# norbi_lm_pl_interface.net
KiCad netlist of a schematic drawn in Altium Designer
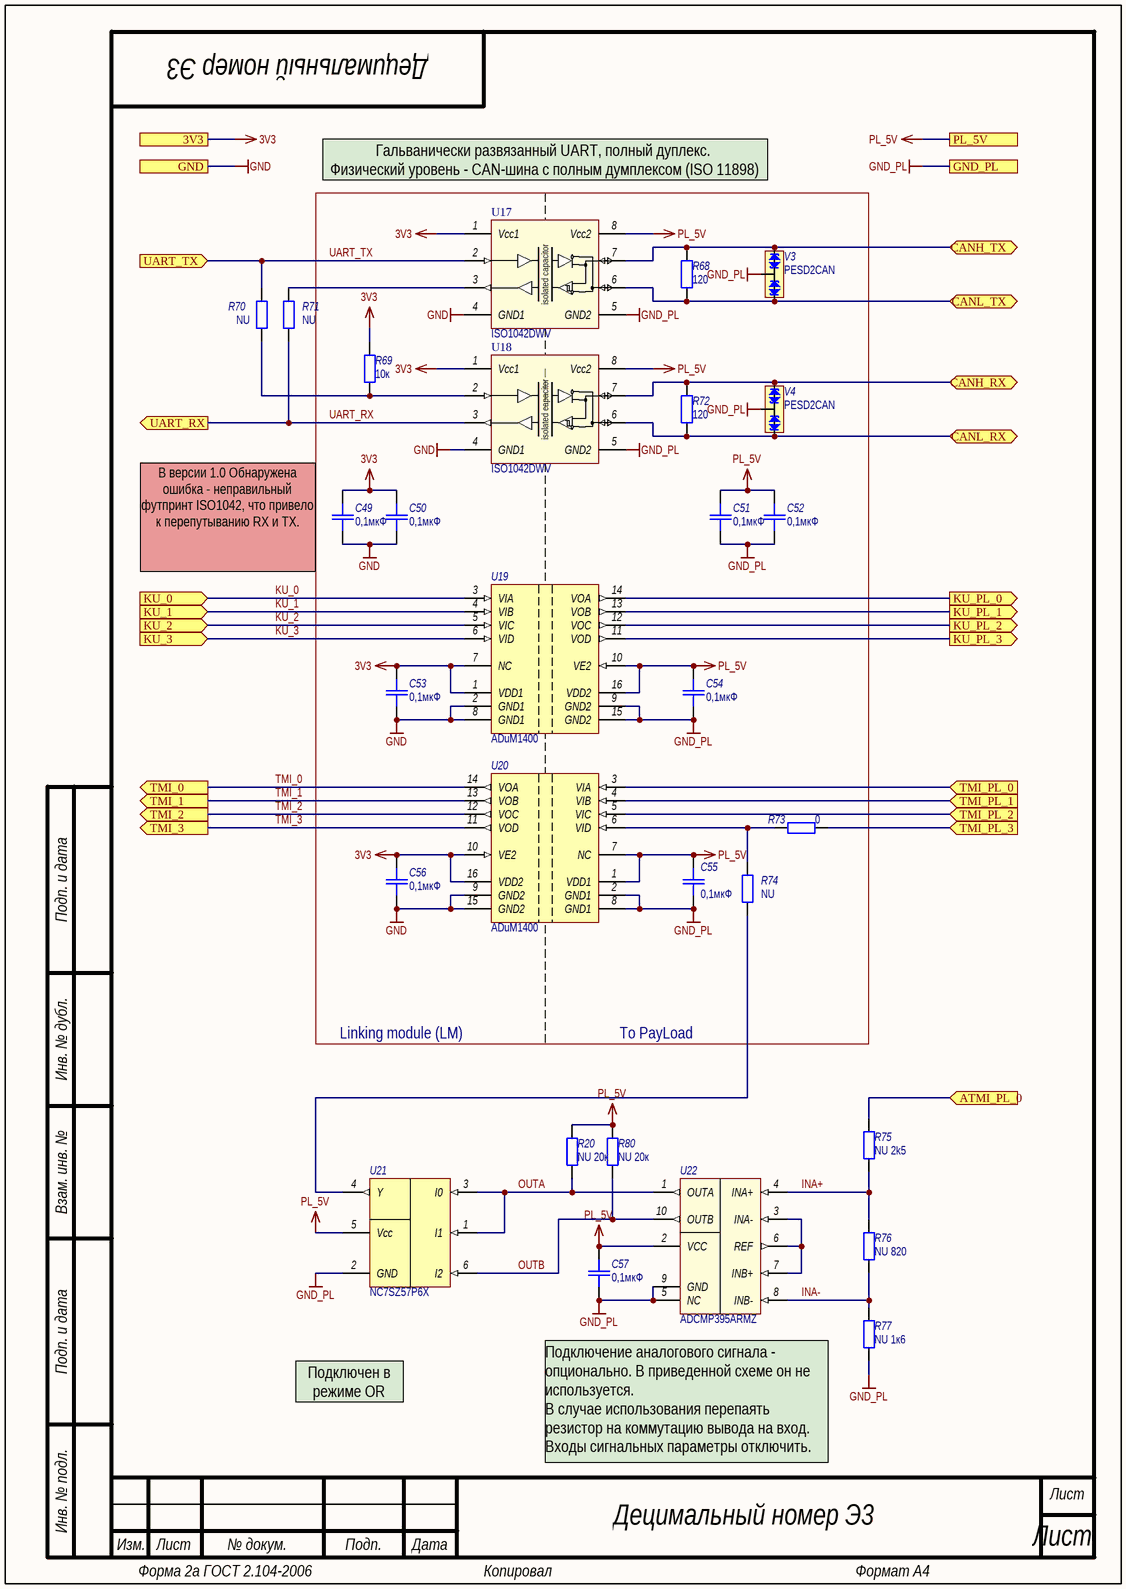
[diagram p0: norbi_lm_pl_interface.SchDoc]

(export (version "E")
  (design (tool "Eeschema 10.0.6"))
  (components
    (comp (ref "C49")
      (value "0,1мкФ")
      (footprint "CR-0603")
      (description "Конденсатор для поверхностного монтажа")
      (libsource (lib "my_passive") (part "C_smd"))
    )
    (comp (ref "C50")
      (value "0,1мкФ")
      (footprint "CR-0603")
      (description "Конденсатор для поверхностного монтажа")
      (libsource (lib "my_passive") (part "C_smd"))
    )
    (comp (ref "C51")
      (value "0,1мкФ")
      (footprint "CR-0603")
      (description "Конденсатор для поверхностного монтажа")
      (libsource (lib "my_passive") (part "C_smd"))
    )
    (comp (ref "C52")
      (value "0,1мкФ")
      (footprint "CR-0603")
      (description "Конденсатор для поверхностного монтажа")
      (libsource (lib "my_passive") (part "C_smd"))
    )
    (comp (ref "C53")
      (value "0,1мкФ")
      (footprint "CR-0603")
      (description "Конденсатор для поверхностного монтажа")
      (libsource (lib "my_passive") (part "C_smd"))
    )
    (comp (ref "C54")
      (value "0,1мкФ")
      (footprint "CR-0603")
      (description "Конденсатор для поверхностного монтажа")
      (libsource (lib "my_passive") (part "C_smd"))
    )
    (comp (ref "C55")
      (value "0,1мкФ")
      (footprint "CR-0603")
      (description "Конденсатор для поверхностного монтажа")
      (libsource (lib "my_passive") (part "C_smd"))
    )
    (comp (ref "C56")
      (value "0,1мкФ")
      (footprint "CR-0603")
      (description "Конденсатор для поверхностного монтажа")
      (libsource (lib "my_passive") (part "C_smd"))
    )
    (comp (ref "C57")
      (value "0,1мкФ")
      (footprint "CR-0603")
      (description "Конденсатор для поверхностного монтажа")
      (libsource (lib "my_passive") (part "C_smd"))
    )
    (comp (ref "R20")
      (value "NU 20к")
      (footprint "CR-0603")
      (description "Резистор для поверхностного монтажа")
      (libsource (lib "my_passive") (part "R_smd"))
    )
    (comp (ref "R68")
      (value "120")
      (footprint "CR-0603")
      (description "Резистор для поверхностного монтажа")
      (libsource (lib "my_passive") (part "R_smd"))
    )
    (comp (ref "R69")
      (value "10к")
      (footprint "CR-0603")
      (description "Резистор для поверхностного монтажа")
      (libsource (lib "") (part "R_smd_1"))
    )
    (comp (ref "R70")
      (value "NU")
      (footprint "CR-0603")
      (description "Резистор для поверхностного монтажа")
      (libsource (lib "my_passive") (part "R_smd"))
    )
    (comp (ref "R71")
      (value "NU")
      (footprint "CR-0603")
      (description "Резистор для поверхностного монтажа")
      (libsource (lib "my_passive") (part "R_smd"))
    )
    (comp (ref "R72")
      (value "120")
      (footprint "CR-0603")
      (description "Резистор для поверхностного монтажа")
      (libsource (lib "my_passive") (part "R_smd"))
    )
    (comp (ref "R73")
      (value "0")
      (footprint "CR-0603")
      (description "Резистор для поверхностного монтажа")
      (libsource (lib "") (part "R_smd_2"))
    )
    (comp (ref "R74")
      (value "NU")
      (footprint "CR-0603")
      (description "Резистор для поверхностного монтажа")
      (libsource (lib "my_passive") (part "R_smd"))
    )
    (comp (ref "R75")
      (value "NU 2k5")
      (footprint "CR-0603")
      (description "Резистор для поверхностного монтажа")
      (libsource (lib "my_passive") (part "R_smd"))
    )
    (comp (ref "R76")
      (value "NU 820")
      (footprint "CR-0603")
      (description "Резистор для поверхностного монтажа")
      (libsource (lib "my_passive") (part "R_smd"))
    )
    (comp (ref "R77")
      (value "NU 1к6")
      (footprint "CR-0603")
      (description "Резистор для поверхностного монтажа")
      (libsource (lib "my_passive") (part "R_smd"))
    )
    (comp (ref "R80")
      (value "NU 20к")
      (footprint "CR-0603")
      (description "Резистор для поверхностного монтажа")
      (libsource (lib "my_passive") (part "R_smd"))
    )
    (comp (ref "U17")
      (value "ISO1042")
      (footprint "SOIC-8-WIDE")
      (description "Isolated CAN Transceiver")
      (fields (field (name "НАИМЕНОВАНИЕ") "ISO1042DWV"))
      (libsource (lib "my_integrated_circuit") (part "ISO1042"))
    )
    (comp (ref "U18")
      (value "ISO1042")
      (footprint "SOIC-8-WIDE")
      (description "Isolated CAN Transceiver")
      (fields (field (name "НАИМЕНОВАНИЕ") "ISO1042DWV"))
      (libsource (lib "my_integrated_circuit") (part "ISO1042"))
    )
    (comp (ref "U19")
      (value "ADuM1400")
      (footprint "SOIC-16-WIDE")
      (description "Quad Channel Digital Isolator, 2.5 KV rms Insulation Rating")
      (fields (field (name "НАИМЕНОВАНИЕ") "ADuM1400"))
      (libsource (lib "") (part "ADuM1400_1"))
    )
    (comp (ref "U20")
      (value "ADuM1400")
      (footprint "SOIC-16-WIDE")
      (description "Quad Channel Digital Isolator, 2.5 KV rms Insulation Rating")
      (fields (field (name "НАИМЕНОВАНИЕ") "ADuM1400"))
      (libsource (lib "my_integrated_circuit") (part "ADuM1400"))
    )
    (comp (ref "U21")
      (value "NC7SZ57P6X")
      (footprint "SC70 6-Lead")
      (description "Universal Configurable 2-Input\r\nLogic Gates")
      (fields (field (name "НАИМЕНОВАНИЕ") "NC7SZ57P6X"))
      (libsource (lib "my_integrated_circuit") (part "NC7SZ57"))
    )
    (comp (ref "U22")
      (value "ADCMP395ARMZ")
      (footprint "MSOP-10")
      (description "Dual Comparators with Accurate Reference Output")
      (fields (field (name "НАИМЕНОВАНИЕ") "ADCMP395ARMZ"))
      (libsource (lib "my_integrated_circuit") (part "ADCMP395"))
    )
    (comp (ref "V3")
      (value "PESD2CAN")
      (footprint "SOT-23")
      (description "CAN bus ESD protection diode")
      (fields (field (name "НАИМЕНОВАНИЕ") "PESD2CAN"))
      (libsource (lib "my_semicond") (part "PESD2CAN"))
    )
    (comp (ref "V4")
      (value "PESD2CAN")
      (footprint "SOT-23")
      (description "CAN bus ESD protection diode")
      (fields (field (name "НАИМЕНОВАНИЕ") "PESD2CAN"))
      (libsource (lib "my_semicond") (part "PESD2CAN"))
    )
  )
  (nets
    (net (code "1") (name "/ATMI_PL_0") (class "Default")
      (node (ref "R75") (pin "2") (pinfunction "2_2") (pintype "passive"))
    )
    (net (code "2") (name "/CANH_RX") (class "Default")
      (node (ref "R72") (pin "2") (pinfunction "2_2") (pintype "passive"))
      (node (ref "U18") (pin "7") (pinfunction "CANH_7") (pintype "bidirectional"))
      (node (ref "V4") (pin "1") (pinfunction "C1_1") (pintype "passive"))
    )
    (net (code "3") (name "/CANH_TX") (class "Default")
      (node (ref "R68") (pin "2") (pinfunction "2_2") (pintype "passive"))
      (node (ref "U17") (pin "7") (pinfunction "CANH_7") (pintype "bidirectional"))
      (node (ref "V3") (pin "1") (pinfunction "C1_1") (pintype "passive"))
    )
    (net (code "4") (name "/CANL_RX") (class "Default")
      (node (ref "R72") (pin "1") (pinfunction "1_1") (pintype "passive"))
      (node (ref "U18") (pin "6") (pinfunction "CANL_6") (pintype "bidirectional"))
      (node (ref "V4") (pin "2") (pinfunction "C2_2") (pintype "passive"))
    )
    (net (code "5") (name "/CANL_TX") (class "Default")
      (node (ref "R68") (pin "1") (pinfunction "1_1") (pintype "passive"))
      (node (ref "U17") (pin "6") (pinfunction "CANL_6") (pintype "bidirectional"))
      (node (ref "V3") (pin "2") (pinfunction "C2_2") (pintype "passive"))
    )
    (net (code "6") (name "/INA+") (class "Default")
      (node (ref "R75") (pin "1") (pinfunction "1_1") (pintype "passive"))
      (node (ref "R76") (pin "2") (pinfunction "2_2") (pintype "passive"))
      (node (ref "U22") (pin "4") (pinfunction "INA+_4") (pintype "input"))
    )
    (net (code "7") (name "/INA-") (class "Default")
      (node (ref "R76") (pin "1") (pinfunction "1_1") (pintype "passive"))
      (node (ref "R77") (pin "2") (pinfunction "2_2") (pintype "passive"))
      (node (ref "U22") (pin "8") (pinfunction "INB-_8") (pintype "input"))
    )
    (net (code "8") (name "/KU_0") (class "Default")
      (node (ref "U19") (pin "3") (pinfunction "VIA_3") (pintype "input"))
    )
    (net (code "9") (name "/KU_1") (class "Default")
      (node (ref "U19") (pin "4") (pinfunction "VIB_4") (pintype "input"))
    )
    (net (code "10") (name "/KU_2") (class "Default")
      (node (ref "U19") (pin "5") (pinfunction "VIC_5") (pintype "input"))
    )
    (net (code "11") (name "/KU_3") (class "Default")
      (node (ref "U19") (pin "6") (pinfunction "VID_6") (pintype "input"))
    )
    (net (code "12") (name "/KU_PL_0") (class "Default")
      (node (ref "U19") (pin "14") (pinfunction "VOA_14") (pintype "output"))
    )
    (net (code "13") (name "/KU_PL_1") (class "Default")
      (node (ref "U19") (pin "13") (pinfunction "VOB_13") (pintype "output"))
    )
    (net (code "14") (name "/KU_PL_2") (class "Default")
      (node (ref "U19") (pin "12") (pinfunction "VOC_12") (pintype "output"))
    )
    (net (code "15") (name "/KU_PL_3") (class "Default")
      (node (ref "U19") (pin "11") (pinfunction "VOD_11") (pintype "output"))
    )
    (net (code "16") (name "/OUTA") (class "Default")
      (node (ref "R20") (pin "1") (pinfunction "1_1") (pintype "passive"))
      (node (ref "U21") (pin "1") (pinfunction "I1_1") (pintype "input"))
      (node (ref "U21") (pin "3") (pinfunction "I0_3") (pintype "input"))
      (node (ref "U22") (pin "1") (pinfunction "OUTA_1") (pintype "output"))
    )
    (net (code "17") (name "/OUTB") (class "Default")
      (node (ref "R80") (pin "1") (pinfunction "1_1") (pintype "passive"))
      (node (ref "U21") (pin "6") (pinfunction "I2_6") (pintype "input"))
      (node (ref "U22") (pin "10") (pinfunction "OUTB_10") (pintype "output"))
    )
    (net (code "18") (name "/TMI_0") (class "Default")
      (node (ref "U20") (pin "14") (pinfunction "VOA_14") (pintype "output"))
    )
    (net (code "19") (name "/TMI_1") (class "Default")
      (node (ref "U20") (pin "13") (pinfunction "VOB_13") (pintype "output"))
    )
    (net (code "20") (name "/TMI_2") (class "Default")
      (node (ref "U20") (pin "12") (pinfunction "VOC_12") (pintype "output"))
    )
    (net (code "21") (name "/TMI_3") (class "Default")
      (node (ref "U20") (pin "11") (pinfunction "VOD_11") (pintype "output"))
    )
    (net (code "22") (name "/TMI_PL_0") (class "Default")
      (node (ref "U20") (pin "3") (pinfunction "VIA_3") (pintype "input"))
    )
    (net (code "23") (name "/TMI_PL_1") (class "Default")
      (node (ref "U20") (pin "4") (pinfunction "VIB_4") (pintype "input"))
    )
    (net (code "24") (name "/TMI_PL_2") (class "Default")
      (node (ref "U20") (pin "5") (pinfunction "VIC_5") (pintype "input"))
    )
    (net (code "25") (name "/TMI_PL_3") (class "Default")
      (node (ref "R73") (pin "1") (pinfunction "1_1") (pintype "passive"))
    )
    (net (code "26") (name "/UART_RX") (class "Default")
      (node (ref "R71") (pin "1") (pinfunction "1_1") (pintype "passive"))
      (node (ref "U18") (pin "3") (pinfunction "RXD_3") (pintype "output"))
    )
    (net (code "27") (name "/UART_TX") (class "Default")
      (node (ref "R70") (pin "2") (pinfunction "2_2") (pintype "passive"))
      (node (ref "U17") (pin "2") (pinfunction "TXD_2") (pintype "input"))
    )
    (net (code "28") (name "3V3") (class "Default")
      (node (ref "C49") (pin "2") (pinfunction "2_2") (pintype "passive"))
      (node (ref "C50") (pin "2") (pinfunction "2_2") (pintype "passive"))
      (node (ref "C53") (pin "2") (pinfunction "2_2") (pintype "passive"))
      (node (ref "C56") (pin "2") (pinfunction "2_2") (pintype "passive"))
      (node (ref "R69") (pin "1") (pinfunction "1_1") (pintype "passive"))
      (node (ref "U17") (pin "1") (pinfunction "Vcc1_1") (pintype "power_in"))
      (node (ref "U18") (pin "1") (pinfunction "Vcc1_1") (pintype "power_in"))
      (node (ref "U19") (pin "1") (pinfunction "VDD1_1") (pintype "power_in"))
      (node (ref "U19") (pin "7") (pinfunction "NC_7") (pintype "passive"))
      (node (ref "U20") (pin "10") (pinfunction "VE2_10") (pintype "input"))
      (node (ref "U20") (pin "16") (pinfunction "VDD2_16") (pintype "power_in"))
    )
    (net (code "29") (name "GND") (class "Default")
      (node (ref "C49") (pin "1") (pinfunction "1_1") (pintype "passive"))
      (node (ref "C50") (pin "1") (pinfunction "1_1") (pintype "passive"))
      (node (ref "C53") (pin "1") (pinfunction "1_1") (pintype "passive"))
      (node (ref "C56") (pin "1") (pinfunction "1_1") (pintype "passive"))
      (node (ref "U17") (pin "4") (pinfunction "GND1_4") (pintype "power_in"))
      (node (ref "U18") (pin "4") (pinfunction "GND1_4") (pintype "power_in"))
      (node (ref "U19") (pin "2") (pinfunction "GND1_2") (pintype "power_in"))
      (node (ref "U19") (pin "8") (pinfunction "GND1_8") (pintype "power_in"))
      (node (ref "U20") (pin "15") (pinfunction "GND2_15") (pintype "power_in"))
      (node (ref "U20") (pin "9") (pinfunction "GND2_9") (pintype "power_in"))
    )
    (net (code "30") (name "GND_PL") (class "Default")
      (node (ref "C51") (pin "1") (pinfunction "1_1") (pintype "passive"))
      (node (ref "C52") (pin "1") (pinfunction "1_1") (pintype "passive"))
      (node (ref "C54") (pin "1") (pinfunction "1_1") (pintype "passive"))
      (node (ref "C55") (pin "1") (pinfunction "1_1") (pintype "passive"))
      (node (ref "C57") (pin "1") (pinfunction "1_1") (pintype "passive"))
      (node (ref "R77") (pin "1") (pinfunction "1_1") (pintype "passive"))
      (node (ref "U17") (pin "5") (pinfunction "GND2_5") (pintype "power_in"))
      (node (ref "U18") (pin "5") (pinfunction "GND2_5") (pintype "power_in"))
      (node (ref "U19") (pin "15") (pinfunction "GND2_15") (pintype "power_in"))
      (node (ref "U19") (pin "9") (pinfunction "GND2_9") (pintype "power_in"))
      (node (ref "U20") (pin "2") (pinfunction "GND1_2") (pintype "power_in"))
      (node (ref "U20") (pin "8") (pinfunction "GND1_8") (pintype "power_in"))
      (node (ref "U21") (pin "2") (pinfunction "GND_2") (pintype "power_in"))
      (node (ref "U22") (pin "5") (pinfunction "NC_5") (pintype "passive"))
      (node (ref "U22") (pin "9") (pinfunction "GND_9") (pintype "power_in"))
      (node (ref "V3") (pin "3") (pinfunction "CC_3") (pintype "passive"))
      (node (ref "V4") (pin "3") (pinfunction "CC_3") (pintype "passive"))
    )
    (net (code "31") (name "Net-(U17-RXD)") (class "Default")
      (node (ref "R71") (pin "2") (pinfunction "2_2") (pintype "passive"))
      (node (ref "U17") (pin "3") (pinfunction "RXD_3") (pintype "output"))
    )
    (net (code "32") (name "Net-(U18-TXD)") (class "Default")
      (node (ref "R69") (pin "2") (pinfunction "2_2") (pintype "passive"))
      (node (ref "R70") (pin "1") (pinfunction "1_1") (pintype "passive"))
      (node (ref "U18") (pin "2") (pinfunction "TXD_2") (pintype "input"))
    )
    (net (code "33") (name "Net-(U20-VID)") (class "Default")
      (node (ref "R73") (pin "2") (pinfunction "2_2") (pintype "passive"))
      (node (ref "R74") (pin "2") (pinfunction "2_2") (pintype "passive"))
      (node (ref "U20") (pin "6") (pinfunction "VID_6") (pintype "input"))
    )
    (net (code "34") (name "Net-(U21-Y)") (class "Default")
      (node (ref "R74") (pin "1") (pinfunction "1_1") (pintype "passive"))
      (node (ref "U21") (pin "4") (pinfunction "Y_4") (pintype "output"))
    )
    (net (code "35") (name "Net-(U22-INA-)") (class "Default")
      (node (ref "U22") (pin "3") (pinfunction "INA-_3") (pintype "input"))
      (node (ref "U22") (pin "6") (pinfunction "REF_6") (pintype "output"))
      (node (ref "U22") (pin "7") (pinfunction "INB+_7") (pintype "input"))
    )
    (net (code "36") (name "PL_5V") (class "Default")
      (node (ref "C51") (pin "2") (pinfunction "2_2") (pintype "passive"))
      (node (ref "C52") (pin "2") (pinfunction "2_2") (pintype "passive"))
      (node (ref "C54") (pin "2") (pinfunction "2_2") (pintype "passive"))
      (node (ref "C55") (pin "2") (pinfunction "2_2") (pintype "passive"))
      (node (ref "C57") (pin "2") (pinfunction "2_2") (pintype "passive"))
      (node (ref "R20") (pin "2") (pinfunction "2_2") (pintype "passive"))
      (node (ref "R80") (pin "2") (pinfunction "2_2") (pintype "passive"))
      (node (ref "U17") (pin "8") (pinfunction "Vcc2_8") (pintype "power_in"))
      (node (ref "U18") (pin "8") (pinfunction "Vcc2_8") (pintype "power_in"))
      (node (ref "U19") (pin "10") (pinfunction "VE2_10") (pintype "input"))
      (node (ref "U19") (pin "16") (pinfunction "VDD2_16") (pintype "power_in"))
      (node (ref "U20") (pin "1") (pinfunction "VDD1_1") (pintype "power_in"))
      (node (ref "U20") (pin "7") (pinfunction "NC_7") (pintype "passive"))
      (node (ref "U21") (pin "5") (pinfunction "Vcc_5") (pintype "power_in"))
      (node (ref "U22") (pin "2") (pinfunction "VCC_2") (pintype "power_in"))
    )
  )
)
